# Schematic_v30.net
KiCad netlist of a schematic drawn in EAGLE
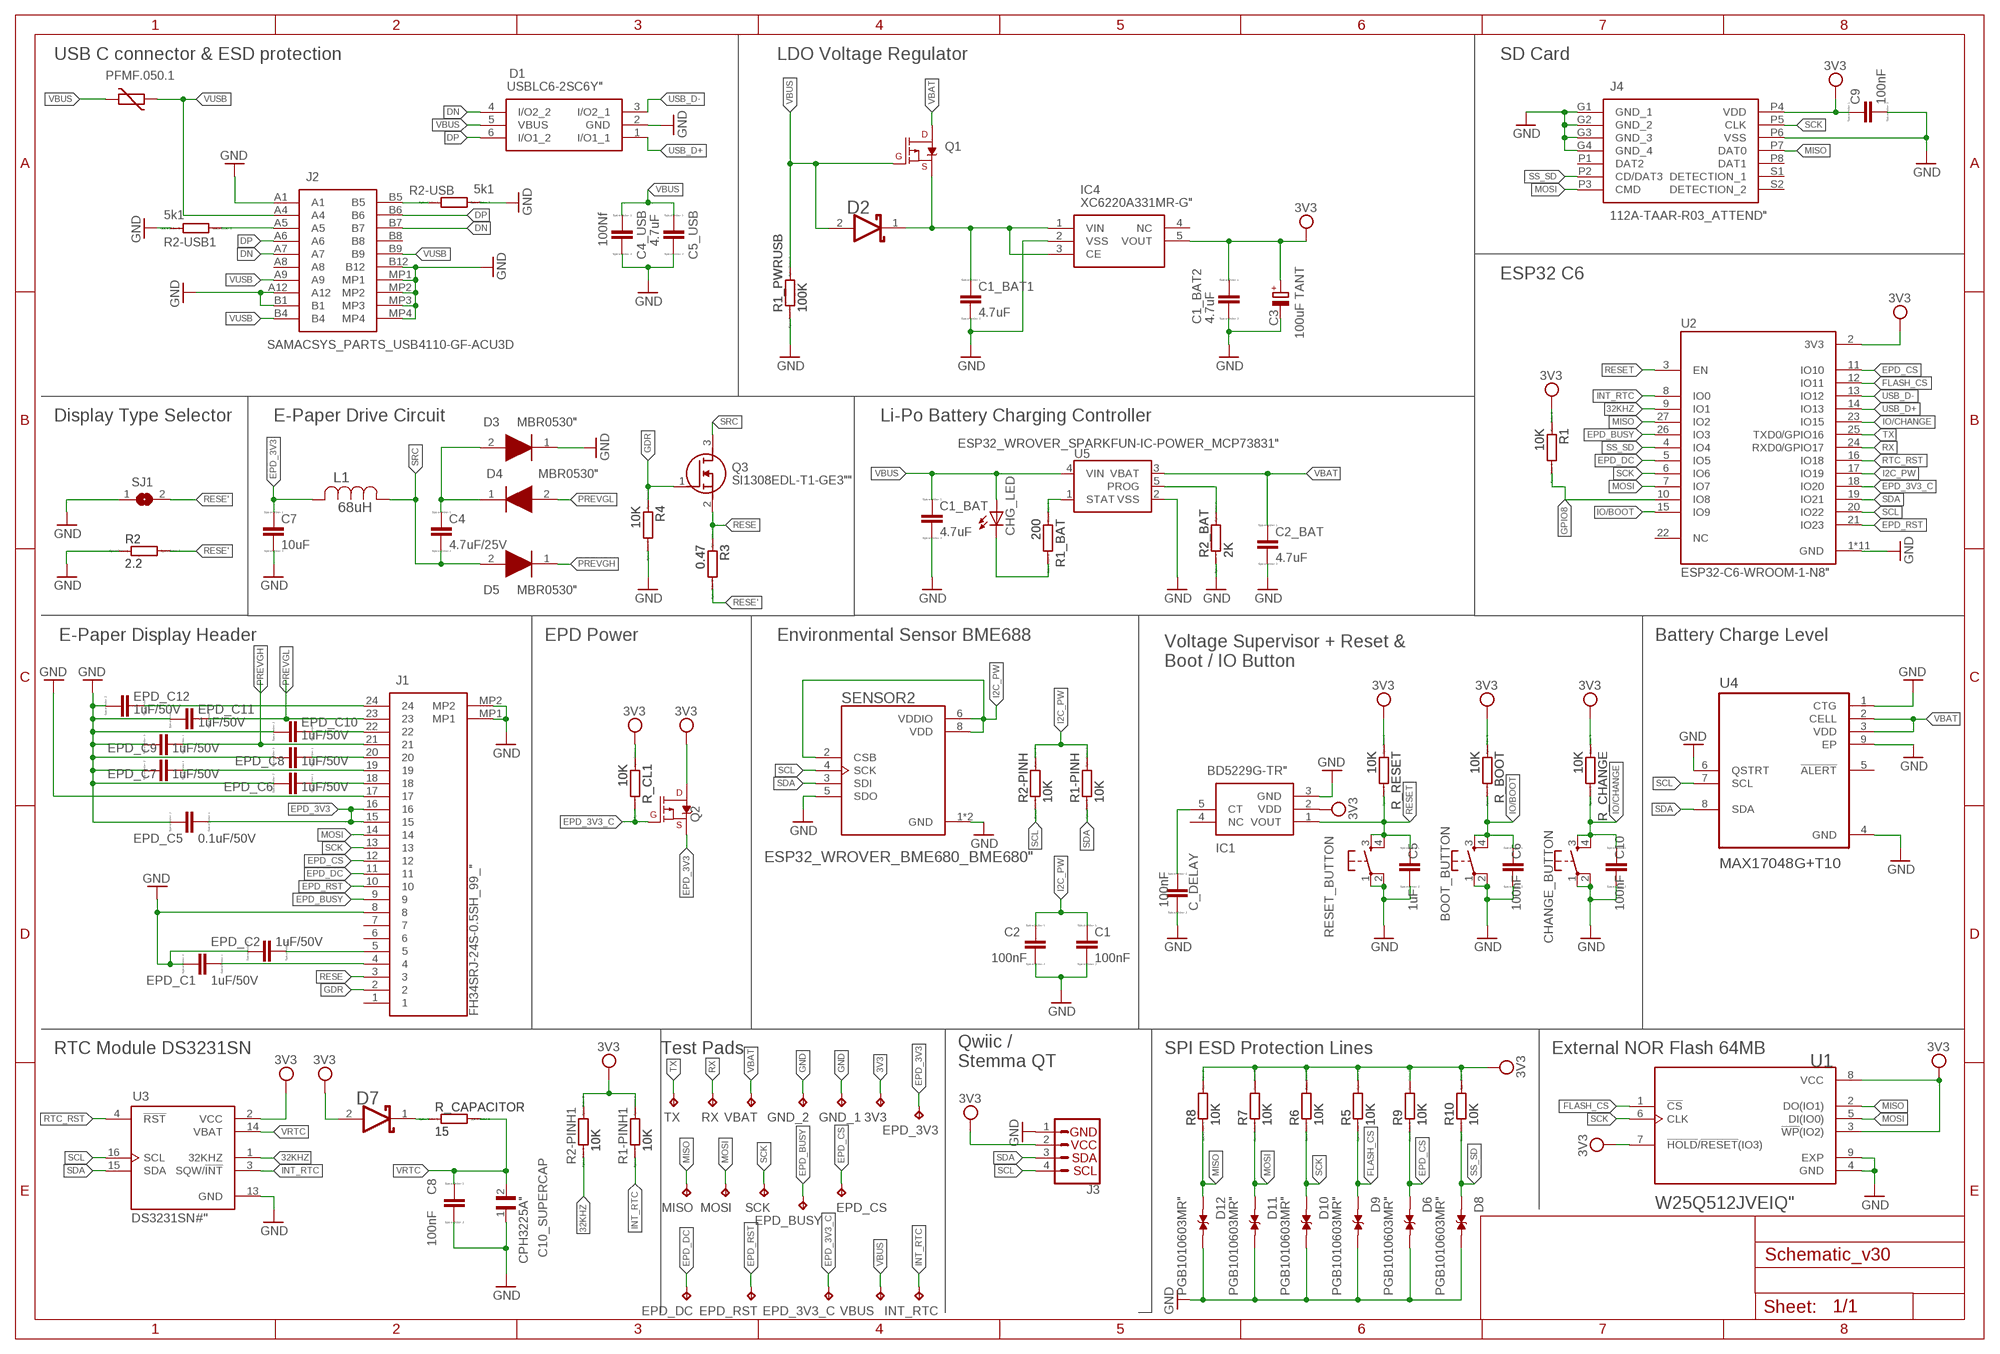
[diagram p0: schematic, sheet 1]

(export (version "E")
  (design (tool "Eeschema 10.0.6"))
  (components
    (comp (ref "3V3")
      (value "TPTP20R")
      (footprint "eagle-import:TP20R")
      (libsource (lib "eagle-import") (part "TPTP20R"))
    )
    (comp (ref "BOOT_BUTTON")
      (value "BUTTON_CUSYOMV1\"")
      (footprint "eagle-import:MYBUTTON")
      (libsource (lib "eagle-import") (part "BUTTON_CUSYOMV1{dblquote}"))
    )
    (comp (ref "C1")
      (value "100nF")
      (footprint "eagle-import:ESP32_WROVER_EAGLE-LTSPICE_C0402")
      (libsource (lib "eagle-import") (part "ESP32_WROVER_EAGLE-LTSPICE_CC0402"))
    )
    (comp (ref "C1_BAT")
      (value "4.7uF")
      (footprint "eagle-import:ESP32_WROVER_EAGLE-LTSPICE_C0402")
      (libsource (lib "eagle-import") (part "ESP32_WROVER_EAGLE-LTSPICE_CC0402"))
    )
    (comp (ref "C1_BAT1")
      (value "4.7uF")
      (footprint "eagle-import:EAGLE-LTSPICE_C0402")
      (libsource (lib "eagle-import") (part "EAGLE-LTSPICE_CC0402"))
    )
    (comp (ref "C1_BAT2")
      (value "4.7uF")
      (footprint "eagle-import:EAGLE-LTSPICE_C0402")
      (libsource (lib "eagle-import") (part "EAGLE-LTSPICE_CC0402"))
    )
    (comp (ref "C2")
      (value "100nF")
      (footprint "eagle-import:ESP32_WROVER_EAGLE-LTSPICE_C0402")
      (libsource (lib "eagle-import") (part "ESP32_WROVER_EAGLE-LTSPICE_CC0402"))
    )
    (comp (ref "C2_BAT")
      (value "4.7uF")
      (footprint "eagle-import:ESP32_WROVER_EAGLE-LTSPICE_C0402")
      (libsource (lib "eagle-import") (part "ESP32_WROVER_EAGLE-LTSPICE_CC0402"))
    )
    (comp (ref "C3")
      (value "100uF TANT")
      (footprint "eagle-import:RCL_CT3528")
      (libsource (lib "eagle-import") (part "RCL_CPOL-EUCT3528"))
    )
    (comp (ref "C4")
      (value "4.7uF/25V")
      (footprint "eagle-import:ESP32_WROVER_EAGLE-LTSPICE_C0402")
      (libsource (lib "eagle-import") (part "ESP32_WROVER_EAGLE-LTSPICE_CC0402"))
    )
    (comp (ref "C4_USB")
      (value "100Nf")
      (footprint "eagle-import:ESP32_WROVER_EAGLE-LTSPICE_C0402")
      (libsource (lib "eagle-import") (part "ESP32_WROVER_EAGLE-LTSPICE_CC0402"))
    )
    (comp (ref "C5")
      (value "1uF")
      (footprint "eagle-import:ESP32_WROVER_EAGLE-LTSPICE_C0402")
      (libsource (lib "eagle-import") (part "ESP32_WROVER_EAGLE-LTSPICE_CC0402"))
    )
    (comp (ref "C5_USB")
      (value "4.7uF")
      (footprint "eagle-import:ESP32_WROVER_EAGLE-LTSPICE_C0402")
      (libsource (lib "eagle-import") (part "ESP32_WROVER_EAGLE-LTSPICE_CC0402"))
    )
    (comp (ref "C6")
      (value "100nF")
      (footprint "eagle-import:ESP32_WROVER_EAGLE-LTSPICE_C0402")
      (libsource (lib "eagle-import") (part "ESP32_WROVER_EAGLE-LTSPICE_CC0402"))
    )
    (comp (ref "C7")
      (value "10uF")
      (footprint "eagle-import:ESP32_WROVER_EAGLE-LTSPICE_C0402")
      (libsource (lib "eagle-import") (part "ESP32_WROVER_EAGLE-LTSPICE_CC0402"))
    )
    (comp (ref "C8")
      (value "100nF")
      (footprint "eagle-import:ESP32_WROVER_EAGLE-LTSPICE_C0402")
      (libsource (lib "eagle-import") (part "ESP32_WROVER_EAGLE-LTSPICE_CC0402"))
    )
    (comp (ref "C9")
      (value "100nF")
      (footprint "eagle-import:EAGLE-LTSPICE_C0402")
      (libsource (lib "eagle-import") (part "EAGLE-LTSPICE_CC0402"))
    )
    (comp (ref "C10")
      (value "100nF")
      (footprint "eagle-import:ESP32_WROVER_EAGLE-LTSPICE_C0402")
      (libsource (lib "eagle-import") (part "ESP32_WROVER_EAGLE-LTSPICE_CC0402"))
    )
    (comp (ref "C10_SUPERCAP")
      (value "CPH3225A\"")
      (footprint "eagle-import:CAPCP3225X100N")
      (libsource (lib "eagle-import") (part "CPH3225A{dblquote}"))
    )
    (comp (ref "CHANGE_BUTTON")
      (value "BUTTON_CUSYOMV1\"")
      (footprint "eagle-import:MYBUTTON")
      (libsource (lib "eagle-import") (part "BUTTON_CUSYOMV1{dblquote}"))
    )
    (comp (ref "CHG_LED")
      (value "ADAFRUIT_LEDCHIP-LED0603")
      (footprint "eagle-import:ADAFRUIT_CHIP-LED0603")
      (libsource (lib "eagle-import") (part "ADAFRUIT_LEDCHIP-LED0603"))
    )
    (comp (ref "C_DELAY")
      (value "100nF")
      (footprint "eagle-import:ESP32_WROVER_EAGLE-LTSPICE_C0402")
      (libsource (lib "eagle-import") (part "ESP32_WROVER_EAGLE-LTSPICE_CC0402"))
    )
    (comp (ref "D1")
      (value "USBLC6-2SC6Y\"")
      (footprint "eagle-import:SOT95P280X145-6N")
      (libsource (lib "eagle-import") (part "USBLC6-2SC6Y{dblquote}"))
    )
    (comp (ref "D2")
      (value "ESP32_WROVER_AVX---SD0805S020S1R0_AVX_SD0805S020S1R0_0_0AVX_SD0805S020S1R0_0_0")
      (footprint "eagle-import:ESP32_WROVER_AVX---SD0805S020S1R0_AVX_SD0805S020S1R0_0")
      (libsource (lib "eagle-import") (part "ESP32_WROVER_AVX---SD0805S020S1R0_AVX_SD0805S020S1R0_0_0AVX_SD0805S020S1R0_0_0"))
    )
    (comp (ref "D3")
      (value "MBR0530\"")
      (footprint "eagle-import:SOD3716X135N")
      (libsource (lib "eagle-import") (part "MBR0530{dblquote}"))
    )
    (comp (ref "D4")
      (value "MBR0530\"")
      (footprint "eagle-import:SOD3716X135N")
      (libsource (lib "eagle-import") (part "MBR0530{dblquote}"))
    )
    (comp (ref "D5")
      (value "MBR0530\"")
      (footprint "eagle-import:SOD3716X135N")
      (libsource (lib "eagle-import") (part "MBR0530{dblquote}"))
    )
    (comp (ref "D6")
      (value "PGB1010603MR\"")
      (footprint "eagle-import:DIOC1608X36N")
      (libsource (lib "eagle-import") (part "PGB1010603MR{dblquote}"))
    )
    (comp (ref "D7")
      (value "ESP32_WROVER_AVX---SD0805S020S1R0_AVX_SD0805S020S1R0_0_0AVX_SD0805S020S1R0_0_0")
      (footprint "eagle-import:ESP32_WROVER_AVX---SD0805S020S1R0_AVX_SD0805S020S1R0_0")
      (libsource (lib "eagle-import") (part "ESP32_WROVER_AVX---SD0805S020S1R0_AVX_SD0805S020S1R0_0_0AVX_SD0805S020S1R0_0_0"))
    )
    (comp (ref "D8")
      (value "PGB1010603MR\"")
      (footprint "eagle-import:DIOC1608X36N")
      (libsource (lib "eagle-import") (part "PGB1010603MR{dblquote}"))
    )
    (comp (ref "D9")
      (value "PGB1010603MR\"")
      (footprint "eagle-import:DIOC1608X36N")
      (libsource (lib "eagle-import") (part "PGB1010603MR{dblquote}"))
    )
    (comp (ref "D10")
      (value "PGB1010603MR\"")
      (footprint "eagle-import:DIOC1608X36N")
      (libsource (lib "eagle-import") (part "PGB1010603MR{dblquote}"))
    )
    (comp (ref "D11")
      (value "PGB1010603MR\"")
      (footprint "eagle-import:DIOC1608X36N")
      (libsource (lib "eagle-import") (part "PGB1010603MR{dblquote}"))
    )
    (comp (ref "D12")
      (value "PGB1010603MR\"")
      (footprint "eagle-import:DIOC1608X36N")
      (libsource (lib "eagle-import") (part "PGB1010603MR{dblquote}"))
    )
    (comp (ref "EPD_3V3")
      (value "TPTP20R")
      (footprint "eagle-import:TP20R")
      (libsource (lib "eagle-import") (part "TPTP20R"))
    )
    (comp (ref "EPD_3V3_C")
      (value "TPTP20R")
      (footprint "eagle-import:TP20R")
      (libsource (lib "eagle-import") (part "TPTP20R"))
    )
    (comp (ref "EPD_BUSY")
      (value "TPTP20R")
      (footprint "eagle-import:TP20R")
      (libsource (lib "eagle-import") (part "TPTP20R"))
    )
    (comp (ref "EPD_C1")
      (value "1uF/50V")
      (footprint "eagle-import:ESP32_WROVER_EAGLE-LTSPICE_C0402")
      (libsource (lib "eagle-import") (part "ESP32_WROVER_EAGLE-LTSPICE_CC0402"))
    )
    (comp (ref "EPD_C2")
      (value "1uF/50V")
      (footprint "eagle-import:ESP32_WROVER_EAGLE-LTSPICE_C0402")
      (libsource (lib "eagle-import") (part "ESP32_WROVER_EAGLE-LTSPICE_CC0402"))
    )
    (comp (ref "EPD_C5")
      (value "0.1uF/50V")
      (footprint "eagle-import:ESP32_WROVER_EAGLE-LTSPICE_C0402")
      (libsource (lib "eagle-import") (part "ESP32_WROVER_EAGLE-LTSPICE_CC0402"))
    )
    (comp (ref "EPD_C6")
      (value "1uF/50V")
      (footprint "eagle-import:ESP32_WROVER_EAGLE-LTSPICE_C0402")
      (libsource (lib "eagle-import") (part "ESP32_WROVER_EAGLE-LTSPICE_CC0402"))
    )
    (comp (ref "EPD_C7")
      (value "1uF/50V")
      (footprint "eagle-import:ESP32_WROVER_EAGLE-LTSPICE_C0402")
      (libsource (lib "eagle-import") (part "ESP32_WROVER_EAGLE-LTSPICE_CC0402"))
    )
    (comp (ref "EPD_C8")
      (value "1uF/50V")
      (footprint "eagle-import:ESP32_WROVER_EAGLE-LTSPICE_C0402")
      (libsource (lib "eagle-import") (part "ESP32_WROVER_EAGLE-LTSPICE_CC0402"))
    )
    (comp (ref "EPD_C9")
      (value "1uF/50V")
      (footprint "eagle-import:ESP32_WROVER_EAGLE-LTSPICE_C0402")
      (libsource (lib "eagle-import") (part "ESP32_WROVER_EAGLE-LTSPICE_CC0402"))
    )
    (comp (ref "EPD_C10")
      (value "1uF/50V")
      (footprint "eagle-import:ESP32_WROVER_EAGLE-LTSPICE_C0402")
      (libsource (lib "eagle-import") (part "ESP32_WROVER_EAGLE-LTSPICE_CC0402"))
    )
    (comp (ref "EPD_C11")
      (value "1uF/50V")
      (footprint "eagle-import:ESP32_WROVER_EAGLE-LTSPICE_C0402")
      (libsource (lib "eagle-import") (part "ESP32_WROVER_EAGLE-LTSPICE_CC0402"))
    )
    (comp (ref "EPD_C12")
      (value "1uF/50V")
      (footprint "eagle-import:ESP32_WROVER_EAGLE-LTSPICE_C0402")
      (libsource (lib "eagle-import") (part "ESP32_WROVER_EAGLE-LTSPICE_CC0402"))
    )
    (comp (ref "EPD_CS")
      (value "TPTP20R")
      (footprint "eagle-import:TP20R")
      (libsource (lib "eagle-import") (part "TPTP20R"))
    )
    (comp (ref "EPD_DC")
      (value "TPTP20R")
      (footprint "eagle-import:TP20R")
      (libsource (lib "eagle-import") (part "TPTP20R"))
    )
    (comp (ref "EPD_RST")
      (value "TPTP20R")
      (footprint "eagle-import:TP20R")
      (libsource (lib "eagle-import") (part "TPTP20R"))
    )
    (comp (ref "GND_1")
      (value "TPTP20R")
      (footprint "eagle-import:TP20R")
      (libsource (lib "eagle-import") (part "TPTP20R"))
    )
    (comp (ref "GND_2")
      (value "TPTP20R")
      (footprint "eagle-import:TP20R")
      (libsource (lib "eagle-import") (part "TPTP20R"))
    )
    (comp (ref "IC1")
      (value "BD5229G-TR\"")
      (footprint "eagle-import:SOT95P280X125-5N")
      (libsource (lib "eagle-import") (part "BD5229G-TR{dblquote}"))
    )
    (comp (ref "IC4")
      (value "XC6220A331MR-G\"")
      (footprint "eagle-import:SOT95P280X120-5N")
      (libsource (lib "eagle-import") (part "XC6220A331MR-G{dblquote}"))
    )
    (comp (ref "INT_RTC")
      (value "TPTP20R")
      (footprint "eagle-import:TP20R")
      (libsource (lib "eagle-import") (part "TPTP20R"))
    )
    (comp (ref "J1")
      (value "FH34SRJ-24S-0.5SH_99_\"")
      (footprint "eagle-import:FH34SRJ24S05SH99")
      (libsource (lib "eagle-import") (part "FH34SRJ-24S-0.5SH_99_{dblquote}"))
    )
    (comp (ref "J2")
      (value "SAMACSYS_PARTS_USB4110-GF-ACU3D")
      (footprint "eagle-import:SAMACSYS_PARTS_USB4110GFA")
      (libsource (lib "eagle-import") (part "SAMACSYS_PARTS_USB4110-GF-ACU3D"))
    )
    (comp (ref "J3")
      (value "QWIIC_RIGHT_ANGLE")
      (footprint "eagle-import:JST04_1MM_RA")
      (libsource (lib "eagle-import") (part "QWIIC_CONNECTORJS-1MM"))
    )
    (comp (ref "J4")
      (value "112A-TAAR-R03_ATTEND\"")
      (footprint "eagle-import:112ATAARR03ATTEND")
      (libsource (lib "eagle-import") (part "112A-TAAR-R03_ATTEND{dblquote}"))
    )
    (comp (ref "L1")
      (value "744043680IND_4828-WE-TPC_WRE")
      (footprint "eagle-import:IND_4828-WE-TPC_WRE")
      (fields (field (name "VAL") "68uH"))
      (libsource (lib "eagle-import") (part "744043680IND_4828-WE-TPC_WRE"))
    )
    (comp (ref "MISO")
      (value "TPTP20R")
      (footprint "eagle-import:TP20R")
      (libsource (lib "eagle-import") (part "TPTP20R"))
    )
    (comp (ref "MOSI")
      (value "TPTP20R")
      (footprint "eagle-import:TP20R")
      (libsource (lib "eagle-import") (part "TPTP20R"))
    )
    (comp (ref "PFMF.050.1")
      (value "ESP32C6_VARISTORCN1812")
      (footprint "eagle-import:ESP32C6_VARISTOR_CT_CN1812")
      (libsource (lib "eagle-import") (part "ESP32C6_VARISTORCN1812"))
    )
    (comp (ref "Q1")
      (value "20V/4.2A/52mΩ/1.4W")
      (footprint "eagle-import:ESP32_WROVER_SPARKFUN-DISCRETESEMI_SOT23-3")
      (libsource (lib "eagle-import") (part "ESP32_WROVER_SPARKFUN-DISCRETESEMI_MOSFET_PCH-DMG2305UX-7"))
    )
    (comp (ref "Q2")
      (value "20V/4.2A/52mΩ/1.4W")
      (footprint "eagle-import:ESP32_WROVER_SPARKFUN-DISCRETESEMI_SOT23-3")
      (libsource (lib "eagle-import") (part "ESP32_WROVER_SPARKFUN-DISCRETESEMI_MOSFET_PCH-DMG2305UX-7"))
    )
    (comp (ref "Q3")
      (value "SI1308EDL-T1-GE3\"\"")
      (footprint "eagle-import:SOT65P210X110-3N")
      (libsource (lib "eagle-import") (part "SI1308EDL-T1-GE3{dblquote}{dblquote}"))
    )
    (comp (ref "R1")
      (value "10K")
      (footprint "eagle-import:ESP32_WROVER_EAGLE-LTSPICE_R0402")
      (libsource (lib "eagle-import") (part "ESP32_WROVER_EAGLE-LTSPICE_RR0402"))
    )
    (comp (ref "R1-PINH")
      (value "10K")
      (footprint "eagle-import:ESP32_WROVER_EAGLE-LTSPICE_R0402")
      (libsource (lib "eagle-import") (part "ESP32_WROVER_EAGLE-LTSPICE_RR0402"))
    )
    (comp (ref "R1-PINH1")
      (value "10K")
      (footprint "eagle-import:ESP32_WROVER_EAGLE-LTSPICE_R0402")
      (libsource (lib "eagle-import") (part "ESP32_WROVER_EAGLE-LTSPICE_RR0402"))
    )
    (comp (ref "R1_BAT")
      (value "200")
      (footprint "eagle-import:ESP32_WROVER_EAGLE-LTSPICE_R0402")
      (libsource (lib "eagle-import") (part "ESP32_WROVER_EAGLE-LTSPICE_RR0402"))
    )
    (comp (ref "R1_PWRUSB")
      (value "100K")
      (footprint "eagle-import:ESP32_WROVER_EAGLE-LTSPICE_R0402")
      (libsource (lib "eagle-import") (part "ESP32_WROVER_EAGLE-LTSPICE_RR0402"))
    )
    (comp (ref "R2")
      (value "2.2")
      (footprint "eagle-import:ESP32_WROVER_EAGLE-LTSPICE_R0402")
      (libsource (lib "eagle-import") (part "ESP32_WROVER_EAGLE-LTSPICE_RR0402"))
    )
    (comp (ref "R2-PINH")
      (value "10K")
      (footprint "eagle-import:ESP32_WROVER_EAGLE-LTSPICE_R0402")
      (libsource (lib "eagle-import") (part "ESP32_WROVER_EAGLE-LTSPICE_RR0402"))
    )
    (comp (ref "R2-PINH1")
      (value "10K")
      (footprint "eagle-import:ESP32_WROVER_EAGLE-LTSPICE_R0402")
      (libsource (lib "eagle-import") (part "ESP32_WROVER_EAGLE-LTSPICE_RR0402"))
    )
    (comp (ref "R2-USB")
      (value "5k1")
      (footprint "eagle-import:ESP32_WROVER_EAGLE-LTSPICE_R0402")
      (libsource (lib "eagle-import") (part "ESP32_WROVER_EAGLE-LTSPICE_RR0402"))
    )
    (comp (ref "R2-USB1")
      (value "5k1")
      (footprint "eagle-import:ESP32_WROVER_EAGLE-LTSPICE_R0402")
      (libsource (lib "eagle-import") (part "ESP32_WROVER_EAGLE-LTSPICE_RR0402"))
    )
    (comp (ref "R2_BAT")
      (value "2K")
      (footprint "eagle-import:ESP32_WROVER_EAGLE-LTSPICE_R0402")
      (libsource (lib "eagle-import") (part "ESP32_WROVER_EAGLE-LTSPICE_RR0402"))
    )
    (comp (ref "R3")
      (value "0.47")
      (footprint "eagle-import:ESP32_WROVER_EAGLE-LTSPICE_R0402")
      (libsource (lib "eagle-import") (part "ESP32_WROVER_EAGLE-LTSPICE_RR0402"))
    )
    (comp (ref "R4")
      (value "10K")
      (footprint "eagle-import:ESP32_WROVER_EAGLE-LTSPICE_R0402")
      (libsource (lib "eagle-import") (part "ESP32_WROVER_EAGLE-LTSPICE_RR0402"))
    )
    (comp (ref "R5")
      (value "10K")
      (footprint "eagle-import:ESP32_WROVER_EAGLE-LTSPICE_R0402")
      (libsource (lib "eagle-import") (part "ESP32_WROVER_EAGLE-LTSPICE_RR0402"))
    )
    (comp (ref "R6")
      (value "10K")
      (footprint "eagle-import:ESP32_WROVER_EAGLE-LTSPICE_R0402")
      (libsource (lib "eagle-import") (part "ESP32_WROVER_EAGLE-LTSPICE_RR0402"))
    )
    (comp (ref "R7")
      (value "10K")
      (footprint "eagle-import:ESP32_WROVER_EAGLE-LTSPICE_R0402")
      (libsource (lib "eagle-import") (part "ESP32_WROVER_EAGLE-LTSPICE_RR0402"))
    )
    (comp (ref "R8")
      (value "10K")
      (footprint "eagle-import:ESP32_WROVER_EAGLE-LTSPICE_R0402")
      (libsource (lib "eagle-import") (part "ESP32_WROVER_EAGLE-LTSPICE_RR0402"))
    )
    (comp (ref "R9")
      (value "10K")
      (footprint "eagle-import:ESP32_WROVER_EAGLE-LTSPICE_R0402")
      (libsource (lib "eagle-import") (part "ESP32_WROVER_EAGLE-LTSPICE_RR0402"))
    )
    (comp (ref "R10")
      (value "10K")
      (footprint "eagle-import:ESP32_WROVER_EAGLE-LTSPICE_R0402")
      (libsource (lib "eagle-import") (part "ESP32_WROVER_EAGLE-LTSPICE_RR0402"))
    )
    (comp (ref "RESET_BUTTON")
      (value "BUTTON_CUSYOMV1\"")
      (footprint "eagle-import:MYBUTTON")
      (libsource (lib "eagle-import") (part "BUTTON_CUSYOMV1{dblquote}"))
    )
    (comp (ref "RX")
      (value "TPTP20R")
      (footprint "eagle-import:TP20R")
      (libsource (lib "eagle-import") (part "TPTP20R"))
    )
    (comp (ref "R_BOOT")
      (value "10K")
      (footprint "eagle-import:ESP32_WROVER_EAGLE-LTSPICE_R0402")
      (libsource (lib "eagle-import") (part "ESP32_WROVER_EAGLE-LTSPICE_RR0402"))
    )
    (comp (ref "R_CAPACITOR")
      (value "15")
      (footprint "eagle-import:ESP32_WROVER_EAGLE-LTSPICE_R0402")
      (libsource (lib "eagle-import") (part "ESP32_WROVER_EAGLE-LTSPICE_RR0402"))
    )
    (comp (ref "R_CHANGE")
      (value "10K")
      (footprint "eagle-import:ESP32_WROVER_EAGLE-LTSPICE_R0402")
      (libsource (lib "eagle-import") (part "ESP32_WROVER_EAGLE-LTSPICE_RR0402"))
    )
    (comp (ref "R_CL1")
      (value "10K")
      (footprint "eagle-import:ESP32_WROVER_EAGLE-LTSPICE_R0402")
      (libsource (lib "eagle-import") (part "ESP32_WROVER_EAGLE-LTSPICE_RR0402"))
    )
    (comp (ref "R_RESET")
      (value "10K")
      (footprint "eagle-import:ESP32_WROVER_EAGLE-LTSPICE_R0402")
      (libsource (lib "eagle-import") (part "ESP32_WROVER_EAGLE-LTSPICE_RR0402"))
    )
    (comp (ref "SCK")
      (value "TPTP20R")
      (footprint "eagle-import:TP20R")
      (libsource (lib "eagle-import") (part "TPTP20R"))
    )
    (comp (ref "SENSOR2")
      (value "ESP32_WROVER_BME680_BME680\"")
      (footprint "eagle-import:ESP32_WROVER_BME680_PSON80P300X300X100-8N")
      (libsource (lib "eagle-import") (part "ESP32_WROVER_BME680_BME680{dblquote}"))
    )
    (comp (ref "SJ1")
      (value "SJ\"\"")
      (footprint "eagle-import:SJ")
      (libsource (lib "eagle-import") (part "SJ{dblquote}{dblquote}"))
    )
    (comp (ref "TX")
      (value "TPTP20R")
      (footprint "eagle-import:TP20R")
      (libsource (lib "eagle-import") (part "TPTP20R"))
    )
    (comp (ref "U1")
      (value "W25Q512JVEIQ\"")
      (footprint "eagle-import:SON127P600X800X80-9N")
      (libsource (lib "eagle-import") (part "W25Q512JVEIQ{dblquote}"))
    )
    (comp (ref "U2")
      (value "ESP32-C6-WROOM-1-N8\"")
      (footprint "eagle-import:XCVR_ESP32-C6-WROOM-1-N8")
      (libsource (lib "eagle-import") (part "ESP32-C6-WROOM-1-N8{dblquote}"))
    )
    (comp (ref "U3")
      (value "DS3231SN#\"")
      (footprint "eagle-import:SOIC127P1032X265-16N")
      (libsource (lib "eagle-import") (part "DS3231SN#{dblquote}"))
    )
    (comp (ref "U4")
      (value "MAX17048G+T10")
      (footprint "eagle-import:SON50P200X200X80-9N")
      (libsource (lib "eagle-import") (part "MAX17048G+T10{dblquote}"))
    )
    (comp (ref "U5")
      (value "ESP32_WROVER_SPARKFUN-IC-POWER_MCP73831\"")
      (footprint "eagle-import:ESP32_WROVER_SPARKFUN-IC-POWER_SOT23-5")
      (libsource (lib "eagle-import") (part "ESP32_WROVER_SPARKFUN-IC-POWER_MCP73831{dblquote}"))
    )
    (comp (ref "VBAT")
      (value "TPTP20R")
      (footprint "eagle-import:TP20R")
      (libsource (lib "eagle-import") (part "TPTP20R"))
    )
    (comp (ref "VBUS")
      (value "TPTP20R")
      (footprint "eagle-import:TP20R")
      (libsource (lib "eagle-import") (part "TPTP20R"))
    )
  )
  (nets
    (net (code "1") (name "3V3") (class "Default")
      (node (ref "3V3") (pin "TP") (pinfunction "TP_TP") (pintype "input"))
      (node (ref "C1_BAT2") (pin "1") (pinfunction "1_1") (pintype "passive"))
      (node (ref "C3") (pin "+") (pinfunction "+_+") (pintype "passive"))
      (node (ref "C9") (pin "1") (pinfunction "1_1") (pintype "passive"))
      (node (ref "D7") (pin "2") (pinfunction "ANODE_2") (pintype "bidirectional"))
      (node (ref "IC1") (pin "2") (pinfunction "VDD_2") (pintype "bidirectional"))
      (node (ref "IC4") (pin "5") (pinfunction "VOUT_5") (pintype "bidirectional"))
      (node (ref "J3") (pin "2") (pinfunction "2_2") (pintype "power_in"))
      (node (ref "J4") (pin "P4") (pinfunction "VDD_P4") (pintype "bidirectional"))
      (node (ref "Q2") (pin "3") (pinfunction "D_3") (pintype "bidirectional"))
      (node (ref "R1") (pin "1") (pinfunction "1_1") (pintype "passive"))
      (node (ref "R1-PINH1") (pin "2") (pinfunction "2_2") (pintype "passive"))
      (node (ref "R10") (pin "2") (pinfunction "2_2") (pintype "passive"))
      (node (ref "R2-PINH1") (pin "2") (pinfunction "2_2") (pintype "passive"))
      (node (ref "R5") (pin "2") (pinfunction "2_2") (pintype "passive"))
      (node (ref "R6") (pin "2") (pinfunction "2_2") (pintype "passive"))
      (node (ref "R7") (pin "2") (pinfunction "2_2") (pintype "passive"))
      (node (ref "R8") (pin "2") (pinfunction "2_2") (pintype "passive"))
      (node (ref "R9") (pin "2") (pinfunction "2_2") (pintype "passive"))
      (node (ref "R_BOOT") (pin "1") (pinfunction "1_1") (pintype "passive"))
      (node (ref "R_CHANGE") (pin "1") (pinfunction "1_1") (pintype "passive"))
      (node (ref "R_CL1") (pin "1") (pinfunction "1_1") (pintype "passive"))
      (node (ref "R_RESET") (pin "1") (pinfunction "1_1") (pintype "passive"))
      (node (ref "U1") (pin "3") (pinfunction "~{WP}(IO2)_3") (pintype "bidirectional"))
      (node (ref "U1") (pin "7") (pinfunction "~{HOLD}/~{RESET}(IO3)_7") (pintype "bidirectional"))
      (node (ref "U1") (pin "8") (pinfunction "VCC_8") (pintype "power_in"))
      (node (ref "U2") (pin "2") (pinfunction "3V3_2") (pintype "power_in"))
      (node (ref "U3") (pin "2") (pinfunction "VCC_2") (pintype "power_in"))
    )
    (net (code "2") (name "32KHZ") (class "Default")
      (node (ref "R2-PINH1") (pin "1") (pinfunction "1_1") (pintype "passive"))
      (node (ref "U2") (pin "9") (pinfunction "IO1_9") (pintype "bidirectional"))
      (node (ref "U3") (pin "1") (pinfunction "32KHZ_1") (pintype "output"))
    )
    (net (code "3") (name "DN") (class "Default")
      (node (ref "D1") (pin "4") (pinfunction "I/O2_2_4") (pintype "bidirectional"))
      (node (ref "J2") (pin "A7") (pinfunction "A7_A7") (pintype "bidirectional"))
      (node (ref "J2") (pin "B7") (pinfunction "B7_B7") (pintype "bidirectional"))
    )
    (net (code "4") (name "DP") (class "Default")
      (node (ref "D1") (pin "6") (pinfunction "I/O1_2_6") (pintype "bidirectional"))
      (node (ref "J2") (pin "A6") (pinfunction "A6_A6") (pintype "bidirectional"))
      (node (ref "J2") (pin "B6") (pinfunction "B6_B6") (pintype "bidirectional"))
    )
    (net (code "5") (name "EPD_3V3") (class "Default")
      (node (ref "C7") (pin "1") (pinfunction "1_1") (pintype "passive"))
      (node (ref "EPD_3V3") (pin "TP") (pinfunction "TP_TP") (pintype "input"))
      (node (ref "EPD_C5") (pin "1") (pinfunction "1_1") (pintype "passive"))
      (node (ref "J1") (pin "15") (pinfunction "15_15") (pintype "bidirectional"))
      (node (ref "J1") (pin "16") (pinfunction "16_16") (pintype "bidirectional"))
      (node (ref "L1") (pin "2") (pinfunction "2_2") (pintype "passive"))
      (node (ref "Q2") (pin "2") (pinfunction "S_2") (pintype "bidirectional"))
    )
    (net (code "6") (name "EPD_3V3_C") (class "Default")
      (node (ref "EPD_3V3_C") (pin "TP") (pinfunction "TP_TP") (pintype "input"))
      (node (ref "Q2") (pin "1") (pinfunction "G_1") (pintype "bidirectional"))
      (node (ref "R_CL1") (pin "2") (pinfunction "2_2") (pintype "passive"))
      (node (ref "U2") (pin "18") (pinfunction "IO20_18") (pintype "bidirectional"))
    )
    (net (code "7") (name "EPD_BUSY") (class "Default")
      (node (ref "EPD_BUSY") (pin "TP") (pinfunction "TP_TP") (pintype "input"))
      (node (ref "J1") (pin "9") (pinfunction "9_9") (pintype "bidirectional"))
      (node (ref "U2") (pin "26") (pinfunction "IO3_26") (pintype "bidirectional"))
    )
    (net (code "8") (name "EPD_CS") (class "Default")
      (node (ref "D6") (pin "1") (pinfunction "1_1") (pintype "passive"))
      (node (ref "EPD_CS") (pin "TP") (pinfunction "TP_TP") (pintype "input"))
      (node (ref "J1") (pin "12") (pinfunction "12_12") (pintype "bidirectional"))
      (node (ref "R9") (pin "1") (pinfunction "1_1") (pintype "passive"))
      (node (ref "U2") (pin "11") (pinfunction "IO10_11") (pintype "bidirectional"))
    )
    (net (code "9") (name "EPD_DC") (class "Default")
      (node (ref "EPD_DC") (pin "TP") (pinfunction "TP_TP") (pintype "input"))
      (node (ref "J1") (pin "11") (pinfunction "11_11") (pintype "bidirectional"))
      (node (ref "U2") (pin "5") (pinfunction "IO5_5") (pintype "bidirectional"))
    )
    (net (code "10") (name "EPD_RST") (class "Default")
      (node (ref "EPD_RST") (pin "TP") (pinfunction "TP_TP") (pintype "input"))
      (node (ref "J1") (pin "10") (pinfunction "10_10") (pintype "bidirectional"))
      (node (ref "U2") (pin "21") (pinfunction "IO23_21") (pintype "bidirectional"))
    )
    (net (code "11") (name "FLASH_CS") (class "Default")
      (node (ref "D9") (pin "1") (pinfunction "1_1") (pintype "passive"))
      (node (ref "R5") (pin "1") (pinfunction "1_1") (pintype "passive"))
      (node (ref "U1") (pin "1") (pinfunction "~{CS}_1") (pintype "input"))
      (node (ref "U2") (pin "12") (pinfunction "IO11_12") (pintype "bidirectional"))
    )
    (net (code "12") (name "GDR") (class "Default")
      (node (ref "J1") (pin "2") (pinfunction "2_2") (pintype "bidirectional"))
      (node (ref "Q3") (pin "1") (pinfunction "G_1") (pintype "bidirectional"))
      (node (ref "R4") (pin "1") (pinfunction "1_1") (pintype "passive"))
    )
    (net (code "13") (name "GND") (class "Default")
      (node (ref "BOOT_BUTTON") (pin "1") (pinfunction "1_1") (pintype "passive"))
      (node (ref "BOOT_BUTTON") (pin "2") (pinfunction "2_2") (pintype "passive"))
      (node (ref "C1") (pin "2") (pinfunction "2_2") (pintype "passive"))
      (node (ref "C10") (pin "2") (pinfunction "2_2") (pintype "passive"))
      (node (ref "C10_SUPERCAP") (pin "1") (pinfunction "1_1") (pintype "passive"))
      (node (ref "C1_BAT") (pin "2") (pinfunction "2_2") (pintype "passive"))
      (node (ref "C1_BAT1") (pin "2") (pinfunction "2_2") (pintype "passive"))
      (node (ref "C1_BAT2") (pin "2") (pinfunction "2_2") (pintype "passive"))
      (node (ref "C2") (pin "2") (pinfunction "2_2") (pintype "passive"))
      (node (ref "C2_BAT") (pin "2") (pinfunction "2_2") (pintype "passive"))
      (node (ref "C3") (pin "-") (pinfunction "-_-") (pintype "passive"))
      (node (ref "C4_USB") (pin "2") (pinfunction "2_2") (pintype "passive"))
      (node (ref "C5") (pin "2") (pinfunction "2_2") (pintype "passive"))
      (node (ref "C5_USB") (pin "2") (pinfunction "2_2") (pintype "passive"))
      (node (ref "C6") (pin "2") (pinfunction "2_2") (pintype "passive"))
      (node (ref "C7") (pin "2") (pinfunction "2_2") (pintype "passive"))
      (node (ref "C8") (pin "2") (pinfunction "2_2") (pintype "passive"))
      (node (ref "C9") (pin "2") (pinfunction "2_2") (pintype "passive"))
      (node (ref "CHANGE_BUTTON") (pin "1") (pinfunction "1_1") (pintype "passive"))
      (node (ref "CHANGE_BUTTON") (pin "2") (pinfunction "2_2") (pintype "passive"))
      (node (ref "C_DELAY") (pin "2") (pinfunction "2_2") (pintype "passive"))
      (node (ref "D1") (pin "2") (pinfunction "GND_2") (pintype "bidirectional"))
      (node (ref "D10") (pin "2") (pinfunction "2_2") (pintype "passive"))
      (node (ref "D11") (pin "2") (pinfunction "2_2") (pintype "passive"))
      (node (ref "D12") (pin "2") (pinfunction "2_2") (pintype "passive"))
      (node (ref "D3") (pin "1") (pinfunction "K_1") (pintype "bidirectional"))
      (node (ref "D6") (pin "2") (pinfunction "2_2") (pintype "passive"))
      (node (ref "D8") (pin "2") (pinfunction "2_2") (pintype "passive"))
      (node (ref "D9") (pin "2") (pinfunction "2_2") (pintype "passive"))
      (node (ref "EPD_C1") (pin "2") (pinfunction "2_2") (pintype "passive"))
      (node (ref "EPD_C10") (pin "2") (pinfunction "2_2") (pintype "passive"))
      (node (ref "EPD_C11") (pin "2") (pinfunction "2_2") (pintype "passive"))
      (node (ref "EPD_C12") (pin "2") (pinfunction "2_2") (pintype "passive"))
      (node (ref "EPD_C2") (pin "2") (pinfunction "2_2") (pintype "passive"))
      (node (ref "EPD_C5") (pin "2") (pinfunction "2_2") (pintype "passive"))
      (node (ref "EPD_C6") (pin "2") (pinfunction "2_2") (pintype "passive"))
      (node (ref "EPD_C7") (pin "2") (pinfunction "2_2") (pintype "passive"))
      (node (ref "EPD_C8") (pin "2") (pinfunction "2_2") (pintype "passive"))
      (node (ref "EPD_C9") (pin "2") (pinfunction "2_2") (pintype "passive"))
      (node (ref "GND_1") (pin "TP") (pinfunction "TP_TP") (pintype "input"))
      (node (ref "GND_2") (pin "TP") (pinfunction "TP_TP") (pintype "input"))
      (node (ref "IC1") (pin "3") (pinfunction "GND_3") (pintype "bidirectional"))
      (node (ref "IC4") (pin "2") (pinfunction "VSS_2") (pintype "bidirectional"))
      (node (ref "J1") (pin "17") (pinfunction "17_17") (pintype "bidirectional"))
      (node (ref "J1") (pin "8") (pinfunction "8_8") (pintype "bidirectional"))
      (node (ref "J1") (pin "MP1") (pinfunction "MP1_MP1") (pintype "bidirectional"))
      (node (ref "J1") (pin "MP2") (pinfunction "MP2_MP2") (pintype "bidirectional"))
      (node (ref "J2") (pin "A1") (pinfunction "A1_A1") (pintype "bidirectional"))
      (node (ref "J2") (pin "A12") (pinfunction "A12_A12") (pintype "bidirectional"))
      (node (ref "J2") (pin "B1") (pinfunction "B1_B1") (pintype "bidirectional"))
      (node (ref "J2") (pin "B12") (pinfunction "B12_B12") (pintype "bidirectional"))
      (node (ref "J2") (pin "MP1") (pinfunction "MP1_MP1") (pintype "bidirectional"))
      (node (ref "J2") (pin "MP2") (pinfunction "MP2_MP2") (pintype "bidirectional"))
      (node (ref "J2") (pin "MP3") (pinfunction "MP3_MP3") (pintype "bidirectional"))
      (node (ref "J2") (pin "MP4") (pinfunction "MP4_MP4") (pintype "bidirectional"))
      (node (ref "J3") (pin "1") (pinfunction "1_1") (pintype "power_in"))
      (node (ref "J4") (pin "G1") (pinfunction "GND_1_G1") (pintype "bidirectional"))
      (node (ref "J4") (pin "G2") (pinfunction "GND_2_G2") (pintype "bidirectional"))
      (node (ref "J4") (pin "G3") (pinfunction "GND_3_G3") (pintype "bidirectional"))
      (node (ref "J4") (pin "G4") (pinfunction "GND_4_G4") (pintype "bidirectional"))
      (node (ref "J4") (pin "P6") (pinfunction "VSS_P6") (pintype "bidirectional"))
      (node (ref "R1_PWRUSB") (pin "1") (pinfunction "1_1") (pintype "passive"))
      (node (ref "R2") (pin "1") (pinfunction "1_1") (pintype "passive"))
      (node (ref "R2-USB") (pin "2") (pinfunction "2_2") (pintype "passive"))
      (node (ref "R2-USB1") (pin "1") (pinfunction "1_1") (pintype "passive"))
      (node (ref "R2_BAT") (pin "1") (pinfunction "1_1") (pintype "passive"))
      (node (ref "R4") (pin "2") (pinfunction "2_2") (pintype "passive"))
      (node (ref "RESET_BUTTON") (pin "1") (pinfunction "1_1") (pintype "passive"))
      (node (ref "RESET_BUTTON") (pin "2") (pinfunction "2_2") (pintype "passive"))
      (node (ref "SENSOR2") (pin "1") (pinfunction "GND_1") (pintype "power_in"))
      (node (ref "SENSOR2") (pin "5") (pinfunction "SDO_5") (pintype "bidirectional"))
      (node (ref "SENSOR2") (pin "7") (pinfunction "GND_7") (pintype "power_in"))
      (node (ref "SJ1") (pin "1") (pinfunction "1_1") (pintype "passive"))
      (node (ref "U1") (pin "4") (pinfunction "GND_4") (pintype "power_in"))
      (node (ref "U1") (pin "9") (pinfunction "EXP_9") (pintype "passive"))
      (node (ref "U2") (pin "1") (pinfunction "GND_1") (pintype "power_in"))
      (node (ref "U2") (pin "28") (pinfunction "GND_28") (pintype "power_in"))
      (node (ref "U2") (pin "29_1") (pinfunction "GND_29_1") (pintype "power_in"))
      (node (ref "U2") (pin "29_2") (pinfunction "GND_29_2") (pintype "power_in"))
      (node (ref "U2") (pin "29_3") (pinfunction "GND_29_3") (pintype "power_in"))
      (node (ref "U2") (pin "29_4") (pinfunction "GND_29_4") (pintype "power_in"))
      (node (ref "U2") (pin "29_5") (pinfunction "GND_29_5") (pintype "power_in"))
      (node (ref "U2") (pin "29_6") (pinfunction "GND_29_6") (pintype "power_in"))
      (node (ref "U2") (pin "29_7") (pinfunction "GND_29_7") (pintype "power_in"))
      (node (ref "U2") (pin "29_8") (pinfunction "GND_29_8") (pintype "power_in"))
      (node (ref "U2") (pin "29_9") (pinfunction "GND_29_9") (pintype "power_in"))
      (node (ref "U3") (pin "13") (pinfunction "GND_13") (pintype "power_in"))
      (node (ref "U4") (pin "1") (pinfunction "CTG_1") (pintype "power_in"))
      (node (ref "U4") (pin "4") (pinfunction "GND_4") (pintype "power_in"))
      (node (ref "U4") (pin "6") (pinfunction "QSTRT_6") (pintype "input"))
      (node (ref "U4") (pin "9") (pinfunction "EP_9") (pintype "power_in"))
      (node (ref "U5") (pin "2") (pinfunction "VSS_2") (pintype "power_in"))
    )
    (net (code "14") (name "GPIO8") (class "Default")
      (node (ref "R1") (pin "2") (pinfunction "2_2") (pintype "passive"))
      (node (ref "U2") (pin "10") (pinfunction "IO8_10") (pintype "bidirectional"))
    )
    (net (code "15") (name "I2C_PW") (class "Default")
      (node (ref "C1") (pin "1") (pinfunction "1_1") (pintype "passive"))
      (node (ref "C2") (pin "1") (pinfunction "1_1") (pintype "passive"))
      (node (ref "R1-PINH") (pin "2") (pinfunction "2_2") (pintype "passive"))
      (node (ref "R2-PINH") (pin "2") (pinfunction "2_2") (pintype "passive"))
      (node (ref "SENSOR2") (pin "2") (pinfunction "CSB_2") (pintype "input"))
      (node (ref "SENSOR2") (pin "6") (pinfunction "VDDIO_6") (pintype "power_in"))
      (node (ref "SENSOR2") (pin "8") (pinfunction "VDD_8") (pintype "power_in"))
      (node (ref "U2") (pin "17") (pinfunction "IO19_17") (pintype "bidirectional"))
    )
    (net (code "16") (name "INT_RTC") (class "Default")
      (node (ref "INT_RTC") (pin "TP") (pinfunction "TP_TP") (pintype "input"))
      (node (ref "R1-PINH1") (pin "1") (pinfunction "1_1") (pintype "passive"))
      (node (ref "U2") (pin "8") (pinfunction "IO0_8") (pintype "bidirectional"))
      (node (ref "U3") (pin "3") (pinfunction "SQW/~{INT}_3") (pintype "output"))
    )
    (net (code "17") (name "IO{slash}BOOT") (class "Default")
      (node (ref "BOOT_BUTTON") (pin "3") (pinfunction "3_3") (pintype "passive"))
      (node (ref "BOOT_BUTTON") (pin "4") (pinfunction "4_4") (pintype "passive"))
      (node (ref "C6") (pin "1") (pinfunction "1_1") (pintype "passive"))
      (node (ref "R_BOOT") (pin "2") (pinfunction "2_2") (pintype "passive"))
      (node (ref "U2") (pin "15") (pinfunction "IO9_15") (pintype "bidirectional"))
    )
    (net (code "18") (name "IO{slash}CHANGE") (class "Default")
      (node (ref "C10") (pin "1") (pinfunction "1_1") (pintype "passive"))
      (node (ref "CHANGE_BUTTON") (pin "3") (pinfunction "3_3") (pintype "passive"))
      (node (ref "CHANGE_BUTTON") (pin "4") (pinfunction "4_4") (pintype "passive"))
      (node (ref "R_CHANGE") (pin "2") (pinfunction "2_2") (pintype "passive"))
      (node (ref "U2") (pin "23") (pinfunction "IO15_23") (pintype "bidirectional"))
    )
    (net (code "19") (name "MISO") (class "Default")
      (node (ref "D12") (pin "1") (pinfunction "1_1") (pintype "passive"))
      (node (ref "J4") (pin "P7") (pinfunction "DAT0_P7") (pintype "bidirectional"))
      (node (ref "MISO") (pin "TP") (pinfunction "TP_TP") (pintype "input"))
      (node (ref "R8") (pin "1") (pinfunction "1_1") (pintype "passive"))
      (node (ref "U1") (pin "2") (pinfunction "DO(IO1)_2") (pintype "bidirectional"))
      (node (ref "U2") (pin "27") (pinfunction "IO2_27") (pintype "bidirectional"))
    )
    (net (code "20") (name "MOSI") (class "Default")
      (node (ref "D11") (pin "1") (pinfunction "1_1") (pintype "passive"))
      (node (ref "J1") (pin "14") (pinfunction "14_14") (pintype "bidirectional"))
      (node (ref "J4") (pin "P3") (pinfunction "CMD_P3") (pintype "bidirectional"))
      (node (ref "MOSI") (pin "TP") (pinfunction "TP_TP") (pintype "input"))
      (node (ref "R7") (pin "1") (pinfunction "1_1") (pintype "passive"))
      (node (ref "U1") (pin "5") (pinfunction "DI(IO0)_5") (pintype "bidirectional"))
      (node (ref "U2") (pin "7") (pinfunction "IO7_7") (pintype "bidirectional"))
    )
    (net (code "21") (name "Net-(CHG_LED-PadC)") (class "Default")
      (node (ref "CHG_LED") (pin "C") (pinfunction "C_C") (pintype "passive"))
      (node (ref "R1_BAT") (pin "2") (pinfunction "2_2") (pintype "passive"))
    )
    (net (code "22") (name "Net-(D2-CATHODE)") (class "Default")
      (node (ref "C1_BAT1") (pin "1") (pinfunction "1_1") (pintype "passive"))
      (node (ref "D2") (pin "1") (pinfunction "CATHODE_1") (pintype "bidirectional"))
      (node (ref "IC4") (pin "1") (pinfunction "VIN_1") (pintype "bidirectional"))
      (node (ref "IC4") (pin "3") (pinfunction "CE_3") (pintype "bidirectional"))
      (node (ref "Q1") (pin "2") (pinfunction "S_2") (pintype "bidirectional"))
    )
    (net (code "23") (name "Net-(D3-A)") (class "Default")
      (node (ref "C4") (pin "1") (pinfunction "1_1") (pintype "passive"))
      (node (ref "D3") (pin "2") (pinfunction "A_2") (pintype "bidirectional"))
      (node (ref "D4") (pin "1") (pinfunction "K_1") (pintype "bidirectional"))
    )
    (net (code "24") (name "Net-(D7-CATHODE)") (class "Default")
      (node (ref "D7") (pin "1") (pinfunction "CATHODE_1") (pintype "bidirectional"))
      (node (ref "R_CAPACITOR") (pin "1") (pinfunction "1_1") (pintype "passive"))
    )
    (net (code "25") (name "Net-(EPD_C1-Pad1)") (class "Default")
      (node (ref "EPD_C1") (pin "1") (pinfunction "1_1") (pintype "passive"))
      (node (ref "J1") (pin "4") (pinfunction "4_4") (pintype "bidirectional"))
    )
    (net (code "26") (name "Net-(EPD_C2-Pad1)") (class "Default")
      (node (ref "EPD_C2") (pin "1") (pinfunction "1_1") (pintype "passive"))
      (node (ref "J1") (pin "5") (pinfunction "5_5") (pintype "bidirectional"))
    )
    (net (code "27") (name "Net-(EPD_C6-Pad1)") (class "Default")
      (node (ref "EPD_C6") (pin "1") (pinfunction "1_1") (pintype "passive"))
      (node (ref "J1") (pin "18") (pinfunction "18_18") (pintype "bidirectional"))
    )
    (net (code "28") (name "Net-(EPD_C7-Pad1)") (class "Default")
      (node (ref "EPD_C7") (pin "1") (pinfunction "1_1") (pintype "passive"))
      (node (ref "J1") (pin "19") (pinfunction "19_19") (pintype "bidirectional"))
    )
    (net (code "29") (name "Net-(EPD_C8-Pad1)") (class "Default")
      (node (ref "EPD_C8") (pin "1") (pinfunction "1_1") (pintype "passive"))
      (node (ref "J1") (pin "20") (pinfunction "20_20") (pintype "bidirectional"))
    )
    (net (code "30") (name "Net-(EPD_C10-Pad1)") (class "Default")
      (node (ref "EPD_C10") (pin "1") (pinfunction "1_1") (pintype "passive"))
      (node (ref "J1") (pin "22") (pinfunction "22_22") (pintype "bidirectional"))
    )
    (net (code "31") (name "Net-(EPD_C12-Pad1)") (class "Default")
      (node (ref "EPD_C12") (pin "1") (pinfunction "1_1") (pintype "passive"))
      (node (ref "J1") (pin "24") (pinfunction "24_24") (pintype "bidirectional"))
    )
    (net (code "32") (name "Net-(IC1-CT)") (class "Default")
      (node (ref "C_DELAY") (pin "1") (pinfunction "1_1") (pintype "passive"))
      (node (ref "IC1") (pin "5") (pinfunction "CT_5") (pintype "bidirectional"))
    )
    (net (code "33") (name "Net-(J2-PadA5)") (class "Default")
      (node (ref "J2") (pin "A5") (pinfunction "A5_A5") (pintype "bidirectional"))
      (node (ref "R2-USB1") (pin "2") (pinfunction "2_2") (pintype "passive"))
    )
    (net (code "34") (name "Net-(J2-PadB5)") (class "Default")
      (node (ref "J2") (pin "B5") (pinfunction "B5_B5") (pintype "bidirectional"))
      (node (ref "R2-USB") (pin "1") (pinfunction "1_1") (pintype "passive"))
    )
    (net (code "35") (name "Net-(U5-PROG)") (class "Default")
      (node (ref "R2_BAT") (pin "2") (pinfunction "2_2") (pintype "passive"))
      (node (ref "U5") (pin "5") (pinfunction "PROG_5") (pintype "input"))
    )
    (net (code "36") (name "Net-(U5-STAT)") (class "Default")
      (node (ref "R1_BAT") (pin "1") (pinfunction "1_1") (pintype "passive"))
      (node (ref "U5") (pin "1") (pinfunction "STAT_1") (pintype "output"))
    )
    (net (code "37") (name "PREVGH") (class "Default")
      (node (ref "D5") (pin "1") (pinfunction "K_1") (pintype "bidirectional"))
      (node (ref "EPD_C9") (pin "1") (pinfunction "1_1") (pintype "passive"))
      (node (ref "J1") (pin "21") (pinfunction "21_21") (pintype "bidirectional"))
    )
    (net (code "38") (name "PREVGL") (class "Default")
      (node (ref "D4") (pin "2") (pinfunction "A_2") (pintype "bidirectional"))
      (node (ref "EPD_C11") (pin "1") (pinfunction "1_1") (pintype "passive"))
      (node (ref "J1") (pin "23") (pinfunction "23_23") (pintype "bidirectional"))
    )
    (net (code "39") (name "RESE") (class "Default")
      (node (ref "J1") (pin "3") (pinfunction "3_3") (pintype "bidirectional"))
      (node (ref "Q3") (pin "2") (pinfunction "S_2") (pintype "bidirectional"))
      (node (ref "R3") (pin "1") (pinfunction "1_1") (pintype "passive"))
    )
    (net (code "40") (name "RESE'") (class "Default")
      (node (ref "R2") (pin "2") (pinfunction "2_2") (pintype "passive"))
      (node (ref "R3") (pin "2") (pinfunction "2_2") (pintype "passive"))
      (node (ref "SJ1") (pin "2") (pinfunction "2_2") (pintype "passive"))
    )
    (net (code "41") (name "RESET") (class "Default")
      (node (ref "C5") (pin "1") (pinfunction "1_1") (pintype "passive"))
      (node (ref "IC1") (pin "1") (pinfunction "VOUT_1") (pintype "bidirectional"))
      (node (ref "RESET_BUTTON") (pin "3") (pinfunction "3_3") (pintype "passive"))
      (node (ref "RESET_BUTTON") (pin "4") (pinfunction "4_4") (pintype "passive"))
      (node (ref "R_RESET") (pin "2") (pinfunction "2_2") (pintype "passive"))
      (node (ref "U2") (pin "3") (pinfunction "EN_3") (pintype "input"))
    )
    (net (code "42") (name "RTC_RST") (class "Default")
      (node (ref "U2") (pin "16") (pinfunction "IO18_16") (pintype "bidirectional"))
      (node (ref "U3") (pin "4") (pinfunction "~{RST}_4") (pintype "input"))
    )
    (net (code "43") (name "RX") (class "Default")
      (node (ref "RX") (pin "TP") (pinfunction "TP_TP") (pintype "input"))
      (node (ref "U2") (pin "24") (pinfunction "RXD0/GPIO17_24") (pintype "bidirectional"))
    )
    (net (code "44") (name "SCK") (class "Default")
      (node (ref "D10") (pin "1") (pinfunction "1_1") (pintype "passive"))
      (node (ref "J1") (pin "13") (pinfunction "13_13") (pintype "bidirectional"))
      (node (ref "J4") (pin "P5") (pinfunction "CLK_P5") (pintype "bidirectional"))
      (node (ref "R6") (pin "1") (pinfunction "1_1") (pintype "passive"))
      (node (ref "SCK") (pin "TP") (pinfunction "TP_TP") (pintype "input"))
      (node (ref "U1") (pin "6") (pinfunction "CLK_6") (pintype "input"))
      (node (ref "U2") (pin "6") (pinfunction "IO6_6") (pintype "bidirectional"))
    )
    (net (code "45") (name "SCL") (class "Default")
      (node (ref "J3") (pin "4") (pinfunction "4_4") (pintype "passive"))
      (node (ref "R2-PINH") (pin "1") (pinfunction "1_1") (pintype "passive"))
      (node (ref "SENSOR2") (pin "4") (pinfunction "SCK_4") (pintype "input"))
      (node (ref "U2") (pin "20") (pinfunction "IO22_20") (pintype "bidirectional"))
      (node (ref "U3") (pin "16") (pinfunction "SCL_16") (pintype "input"))
      (node (ref "U4") (pin "7") (pinfunction "SCL_7") (pintype "input"))
    )
    (net (code "46") (name "SDA") (class "Default")
      (node (ref "J3") (pin "3") (pinfunction "3_3") (pintype "passive"))
      (node (ref "R1-PINH") (pin "1") (pinfunction "1_1") (pintype "passive"))
      (node (ref "SENSOR2") (pin "3") (pinfunction "SDI_3") (pintype "bidirectional"))
      (node (ref "U2") (pin "19") (pinfunction "IO21_19") (pintype "bidirectional"))
      (node (ref "U3") (pin "15") (pinfunction "SDA_15") (pintype "bidirectional"))
      (node (ref "U4") (pin "8") (pinfunction "SDA_8") (pintype "bidirectional"))
    )
    (net (code "47") (name "SRC") (class "Default")
      (node (ref "C4") (pin "2") (pinfunction "2_2") (pintype "passive"))
      (node (ref "D5") (pin "2") (pinfunction "A_2") (pintype "bidirectional"))
      (node (ref "L1") (pin "1") (pinfunction "1_1") (pintype "passive"))
      (node (ref "Q3") (pin "3") (pinfunction "D_3") (pintype "bidirectional"))
    )
    (net (code "48") (name "SS_SD") (class "Default")
      (node (ref "D8") (pin "1") (pinfunction "1_1") (pintype "passive"))
      (node (ref "J4") (pin "P2") (pinfunction "CD/DAT3_P2") (pintype "bidirectional"))
      (node (ref "R10") (pin "1") (pinfunction "1_1") (pintype "passive"))
      (node (ref "U2") (pin "4") (pinfunction "IO4_4") (pintype "bidirectional"))
    )
    (net (code "49") (name "TX") (class "Default")
      (node (ref "TX") (pin "TP") (pinfunction "TP_TP") (pintype "input"))
      (node (ref "U2") (pin "25") (pinfunction "TXD0/GPIO16_25") (pintype "bidirectional"))
    )
    (net (code "50") (name "USB_D+") (class "Default")
      (node (ref "D1") (pin "1") (pinfunction "I/O1_1_1") (pintype "bidirectional"))
      (node (ref "U2") (pin "14") (pinfunction "IO13_14") (pintype "bidirectional"))
    )
    (net (code "51") (name "USB_D-") (class "Default")
      (node (ref "D1") (pin "3") (pinfunction "I/O2_1_3") (pintype "bidirectional"))
      (node (ref "U2") (pin "13") (pinfunction "IO12_13") (pintype "bidirectional"))
    )
    (net (code "52") (name "VBAT") (class "Default")
      (node (ref "C2_BAT") (pin "1") (pinfunction "1_1") (pintype "passive"))
      (node (ref "Q1") (pin "3") (pinfunction "D_3") (pintype "bidirectional"))
      (node (ref "U4") (pin "2") (pinfunction "CELL_2") (pintype "power_in"))
      (node (ref "U4") (pin "3") (pinfunction "VDD_3") (pintype "power_in"))
      (node (ref "U5") (pin "3") (pinfunction "VBAT_3") (pintype "power_in"))
      (node (ref "VBAT") (pin "TP") (pinfunction "TP_TP") (pintype "input"))
    )
    (net (code "53") (name "VBUS") (class "Default")
      (node (ref "C1_BAT") (pin "1") (pinfunction "1_1") (pintype "passive"))
      (node (ref "C4_USB") (pin "1") (pinfunction "1_1") (pintype "passive"))
      (node (ref "C5_USB") (pin "1") (pinfunction "1_1") (pintype "passive"))
      (node (ref "CHG_LED") (pin "A") (pinfunction "A_A") (pintype "passive"))
      (node (ref "D1") (pin "5") (pinfunction "VBUS_5") (pintype "bidirectional"))
      (node (ref "D2") (pin "2") (pinfunction "ANODE_2") (pintype "bidirectional"))
      (node (ref "PFMF.050.1") (pin "2") (pinfunction "2_2") (pintype "passive"))
      (node (ref "Q1") (pin "1") (pinfunction "G_1") (pintype "bidirectional"))
      (node (ref "R1_PWRUSB") (pin "2") (pinfunction "2_2") (pintype "passive"))
      (node (ref "U5") (pin "4") (pinfunction "VIN_4") (pintype "power_in"))
      (node (ref "VBUS") (pin "TP") (pinfunction "TP_TP") (pintype "input"))
    )
    (net (code "54") (name "VRTC") (class "Default")
      (node (ref "C10_SUPERCAP") (pin "2") (pinfunction "2_2") (pintype "passive"))
      (node (ref "C8") (pin "1") (pinfunction "1_1") (pintype "passive"))
      (node (ref "R_CAPACITOR") (pin "2") (pinfunction "2_2") (pintype "passive"))
      (node (ref "U3") (pin "14") (pinfunction "VBAT_14") (pintype "power_in"))
    )
    (net (code "55") (name "VUSB") (class "Default")
      (node (ref "J2") (pin "A4") (pinfunction "A4_A4") (pintype "bidirectional"))
      (node (ref "J2") (pin "A9") (pinfunction "A9_A9") (pintype "bidirectional"))
      (node (ref "J2") (pin "B4") (pinfunction "B4_B4") (pintype "bidirectional"))
      (node (ref "J2") (pin "B9") (pinfunction "B9_B9") (pintype "bidirectional"))
      (node (ref "PFMF.050.1") (pin "1") (pinfunction "1_1") (pintype "passive"))
    )
    (net (code "56") (name "unconnected-(IC1-NC-Pad4)") (class "Default")
      (node (ref "IC1") (pin "4") (pinfunction "NC_4") (pintype "no_connect"))
    )
    (net (code "57") (name "unconnected-(IC4-NC-Pad4)") (class "Default")
      (node (ref "IC4") (pin "4") (pinfunction "NC_4") (pintype "no_connect"))
    )
    (net (code "58") (name "unconnected-(J1-Pad1)") (class "Default")
      (node (ref "J1") (pin "1") (pinfunction "1_1") (pintype "bidirectional"))
    )
    (net (code "59") (name "unconnected-(J1-Pad6)") (class "Default")
      (node (ref "J1") (pin "6") (pinfunction "6_6") (pintype "bidirectional"))
    )
    (net (code "60") (name "unconnected-(J1-Pad7)") (class "Default")
      (node (ref "J1") (pin "7") (pinfunction "7_7") (pintype "bidirectional"))
    )
    (net (code "61") (name "unconnected-(J2-PadA8)") (class "Default")
      (node (ref "J2") (pin "A8") (pinfunction "A8_A8") (pintype "bidirectional"))
    )
    (net (code "62") (name "unconnected-(J2-PadB8)") (class "Default")
      (node (ref "J2") (pin "B8") (pinfunction "B8_B8") (pintype "bidirectional"))
    )
    (net (code "63") (name "unconnected-(J4-DAT1-PadP8)") (class "Default")
      (node (ref "J4") (pin "P8") (pinfunction "DAT1_P8") (pintype "bidirectional"))
    )
    (net (code "64") (name "unconnected-(J4-DAT2-PadP1)") (class "Default")
      (node (ref "J4") (pin "P1") (pinfunction "DAT2_P1") (pintype "bidirectional"))
    )
    (net (code "65") (name "unconnected-(J4-DETECTION_1-PadS1)") (class "Default")
      (node (ref "J4") (pin "S1") (pinfunction "DETECTION_1_S1") (pintype "bidirectional"))
    )
    (net (code "66") (name "unconnected-(J4-DETECTION_2-PadS2)") (class "Default")
      (node (ref "J4") (pin "S2") (pinfunction "DETECTION_2_S2") (pintype "bidirectional"))
    )
    (net (code "67") (name "unconnected-(U2-NC-Pad22)") (class "Default")
      (node (ref "U2") (pin "22") (pinfunction "NC_22") (pintype "no_connect"))
    )
    (net (code "68") (name "unconnected-(U4-~{ALERT}-Pad5)") (class "Default")
      (node (ref "U4") (pin "5") (pinfunction "~{ALERT}_5") (pintype "output"))
    )
  )
)
